# MINI_SAM_D51_015.net
KiCad netlist of a schematic drawn in EAGLE
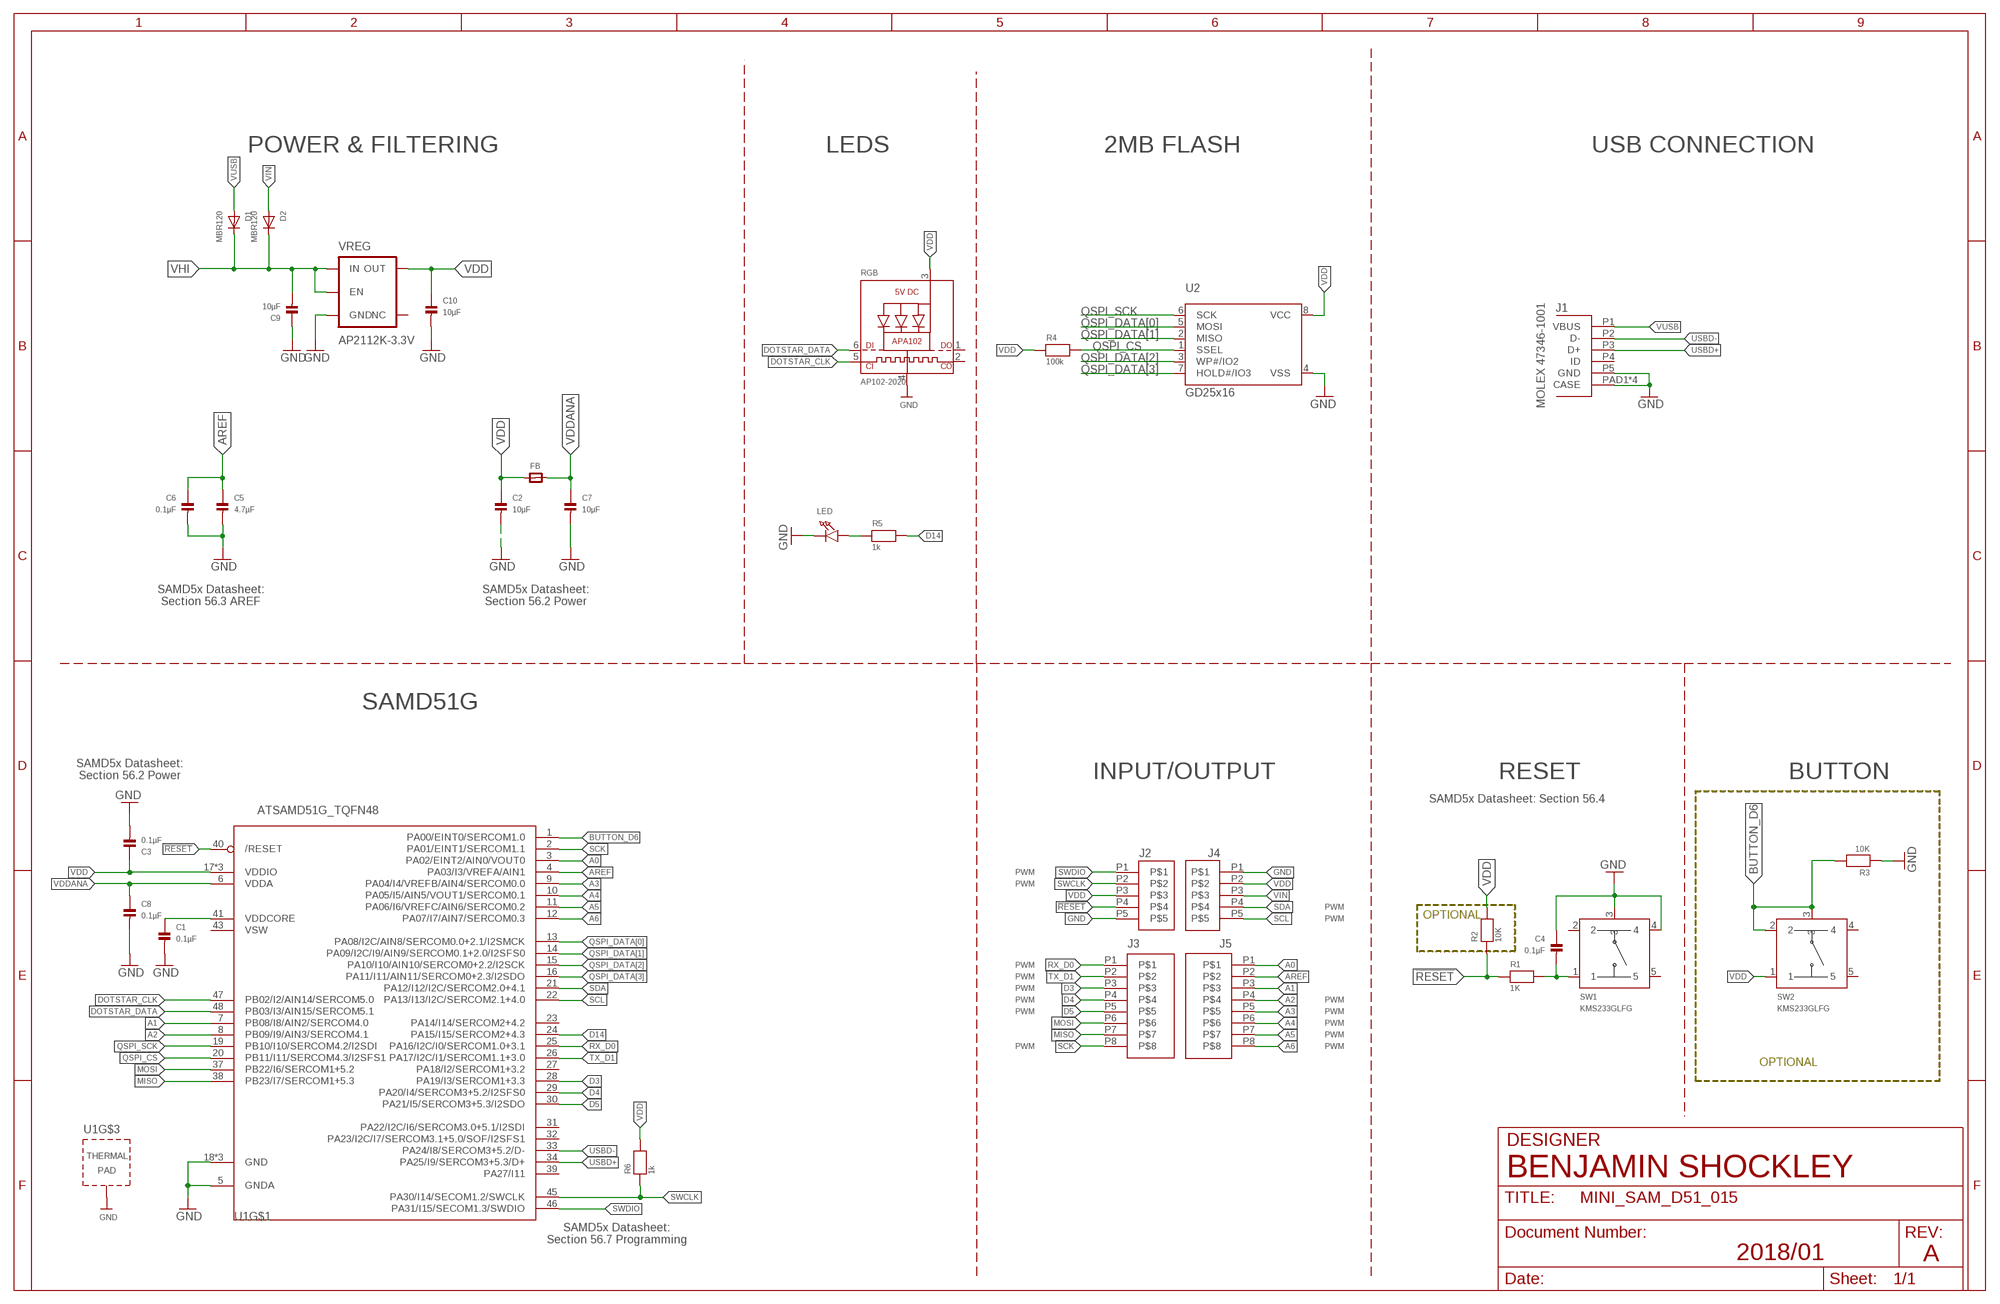
[diagram p0: schematic, sheet 1]

(export (version "E")
  (design (tool "Eeschema 10.0.6"))
  (components
    (comp (ref "C1")
      (value "0.1µF")
      (footprint "eagle-import:_0603MP")
      (libsource (lib "eagle-import") (part "CAP_CERAMIC_0603MP"))
    )
    (comp (ref "C2")
      (value "10µF")
      (footprint "eagle-import:_0603MP")
      (libsource (lib "eagle-import") (part "CAP_CERAMIC_0603MP"))
    )
    (comp (ref "C3")
      (value "0.1µF")
      (footprint "eagle-import:_0603MP")
      (libsource (lib "eagle-import") (part "CAP_CERAMIC_0603MP"))
    )
    (comp (ref "C4")
      (value "0.1µF")
      (footprint "eagle-import:_0603MP")
      (libsource (lib "eagle-import") (part "CAP_CERAMIC_0603MP"))
    )
    (comp (ref "C5")
      (value "4.7µF")
      (footprint "eagle-import:_0603MP")
      (libsource (lib "eagle-import") (part "CAP_CERAMIC_0603MP"))
    )
    (comp (ref "C6")
      (value "0.1µF")
      (footprint "eagle-import:_0603MP")
      (libsource (lib "eagle-import") (part "CAP_CERAMIC_0603MP"))
    )
    (comp (ref "C7")
      (value "10µF")
      (footprint "eagle-import:_0603MP")
      (libsource (lib "eagle-import") (part "CAP_CERAMIC_0603MP"))
    )
    (comp (ref "C8")
      (value "0.1µF")
      (footprint "eagle-import:_0603MP")
      (libsource (lib "eagle-import") (part "CAP_CERAMIC_0603MP"))
    )
    (comp (ref "C9")
      (value "10µF")
      (footprint "eagle-import:_0603MP")
      (libsource (lib "eagle-import") (part "CAP_CERAMIC_0603MP"))
    )
    (comp (ref "C10")
      (value "10µF")
      (footprint "eagle-import:_0603MP")
      (libsource (lib "eagle-import") (part "CAP_CERAMIC_0603MP"))
    )
    (comp (ref "D1")
      (value "MBR120")
      (footprint "eagle-import:SOD-123FL")
      (libsource (lib "eagle-import") (part "DIODE_SOD-123FL"))
    )
    (comp (ref "D2")
      (value "MBR120")
      (footprint "eagle-import:SOD-123FL")
      (libsource (lib "eagle-import") (part "DIODE_SOD-123FL"))
    )
    (comp (ref "FB")
      (value "FERRITE_0603MP")
      (footprint "eagle-import:_0603MP")
      (libsource (lib "eagle-import") (part "FERRITE_0603MP"))
    )
    (comp (ref "J1")
      (value "MOLEX_47346-100147346")
      (footprint "eagle-import:MOLEX_47346-1001")
      (libsource (lib "eagle-import") (part "MOLEX_47346-100147346"))
    )
    (comp (ref "J2")
      (value "1X5_HEADER_1.27MMCAST")
      (footprint "eagle-import:1X5_HEADER_1.27MM_CASTELLATED")
      (libsource (lib "eagle-import") (part "1X5_HEADER_1.27MMCAST"))
    )
    (comp (ref "J3")
      (value "1X8_HEADER_1.27MMCAST")
      (footprint "eagle-import:1X8_HEADER_1.27MM_CASTELLATED")
      (libsource (lib "eagle-import") (part "1X8_HEADER_1.27MMCAST"))
    )
    (comp (ref "J4")
      (value "1X5_HEADER_1.27MMCAST")
      (footprint "eagle-import:1X5_HEADER_1.27MM_CASTELLATED")
      (libsource (lib "eagle-import") (part "1X5_HEADER_1.27MMCAST"))
    )
    (comp (ref "J5")
      (value "1X8_HEADER_1.27MMCAST")
      (footprint "eagle-import:1X8_HEADER_1.27MM_CASTELLATED")
      (libsource (lib "eagle-import") (part "1X8_HEADER_1.27MMCAST"))
    )
    (comp (ref "LED")
      (value "LED0805_NOOUTLINE")
      (footprint "eagle-import:CHIPLED_0805_NOOUTLINE")
      (libsource (lib "eagle-import") (part "LED0805_NOOUTLINE"))
    )
    (comp (ref "R1")
      (value "1K")
      (footprint "eagle-import:_0603MP")
      (libsource (lib "eagle-import") (part "RESISTOR_0603MP"))
    )
    (comp (ref "R2")
      (value "10K")
      (footprint "eagle-import:_0603MP")
      (libsource (lib "eagle-import") (part "RESISTOR_0603MP"))
    )
    (comp (ref "R3")
      (value "10K")
      (footprint "eagle-import:_0603MP")
      (libsource (lib "eagle-import") (part "RESISTOR_0603MP"))
    )
    (comp (ref "R4")
      (value "100k")
      (footprint "eagle-import:_0603MP")
      (libsource (lib "eagle-import") (part "RESISTOR_0603MP"))
    )
    (comp (ref "R5")
      (value "1k")
      (footprint "eagle-import:_0603MP")
      (libsource (lib "eagle-import") (part "RESISTOR_0603MP"))
    )
    (comp (ref "R6")
      (value "1k")
      (footprint "eagle-import:_0603MP")
      (libsource (lib "eagle-import") (part "RESISTOR_0603MP"))
    )
    (comp (ref "RGB")
      (value "AP102-2020")
      (footprint "eagle-import:APA102_2020")
      (libsource (lib "eagle-import") (part "APA1022020"))
    )
    (comp (ref "SW1")
      (value "KMS233GLFG")
      (footprint "eagle-import:KMS_SWITCH")
      (libsource (lib "eagle-import") (part "KMS_SWITCHKMS"))
    )
    (comp (ref "SW2")
      (value "KMS233GLFG")
      (footprint "eagle-import:KMS_SWITCH")
      (libsource (lib "eagle-import") (part "KMS_SWITCHKMS"))
    )
    (comp (ref "U1")
      (value "ATSAMD51G_TQFN48")
      (footprint "eagle-import:TQFN48_7MM")
      (libsource (lib "eagle-import") (part "ATSAMD51G_TQFN48"))
    )
    (comp (ref "U2")
      (value "GD25x16")
      (footprint "eagle-import:USON8")
      (libsource (lib "eagle-import") (part "SPIFLASH_8PINUX"))
    )
    (comp (ref "VREG")
      (value "AP2112K-3.3V")
      (footprint "eagle-import:SOT23-5")
      (libsource (lib "eagle-import") (part "V_REG_AP2112K-3.3V"))
    )
  )
  (nets
    (net (code "1") (name "/VSW") (class "Default")
      (node (ref "U1") (pin "43") (pinfunction "VSW_43") (pintype "power_in"))
    )
    (net (code "2") (name "/~{RESET}") (class "Default")
      (node (ref "J2") (pin "P4") (pinfunction "P$4_P4") (pintype "bidirectional"))
      (node (ref "R1") (pin "1") (pinfunction "1_1") (pintype "passive"))
      (node (ref "R2") (pin "1") (pinfunction "1_1") (pintype "passive"))
      (node (ref "U1") (pin "40") (pinfunction "/RESET_40") (pintype "bidirectional"))
    )
    (net (code "3") (name "A0") (class "Default")
      (node (ref "J5") (pin "P1") (pinfunction "P$1_P1") (pintype "bidirectional"))
      (node (ref "U1") (pin "3") (pinfunction "PA02/EINT2/AIN0/VOUT0_3") (pintype "bidirectional"))
    )
    (net (code "4") (name "A1") (class "Default")
      (node (ref "J5") (pin "P3") (pinfunction "P$3_P3") (pintype "bidirectional"))
      (node (ref "U1") (pin "7") (pinfunction "PB08/I8/AIN2/SERCOM4.0_7") (pintype "bidirectional"))
    )
    (net (code "5") (name "A2") (class "Default")
      (node (ref "J5") (pin "P4") (pinfunction "P$4_P4") (pintype "bidirectional"))
      (node (ref "U1") (pin "8") (pinfunction "PB09/I9/AIN3/SERCOM4.1_8") (pintype "bidirectional"))
    )
    (net (code "6") (name "A3") (class "Default")
      (node (ref "J5") (pin "P5") (pinfunction "P$5_P5") (pintype "bidirectional"))
      (node (ref "U1") (pin "9") (pinfunction "PA04/I4/VREFB/AIN4/SERCOM0.0_9") (pintype "bidirectional"))
    )
    (net (code "7") (name "A4") (class "Default")
      (node (ref "J5") (pin "P6") (pinfunction "P$6_P6") (pintype "bidirectional"))
      (node (ref "U1") (pin "10") (pinfunction "PA05/I5/AIN5/VOUT1/SERCOM0.1_10") (pintype "bidirectional"))
    )
    (net (code "8") (name "A5") (class "Default")
      (node (ref "J5") (pin "P7") (pinfunction "P$7_P7") (pintype "bidirectional"))
      (node (ref "U1") (pin "11") (pinfunction "PA06/I6/VREFC/AIN6/SERCOM0.2_11") (pintype "bidirectional"))
    )
    (net (code "9") (name "A6") (class "Default")
      (node (ref "J5") (pin "P8") (pinfunction "P$8_P8") (pintype "bidirectional"))
      (node (ref "U1") (pin "12") (pinfunction "PA07/I7/AIN7/SERCOM0.3_12") (pintype "bidirectional"))
    )
    (net (code "10") (name "AREF") (class "Default")
      (node (ref "C5") (pin "1") (pinfunction "P$1_1") (pintype "passive"))
      (node (ref "C6") (pin "1") (pinfunction "P$1_1") (pintype "passive"))
      (node (ref "J5") (pin "P2") (pinfunction "P$2_P2") (pintype "bidirectional"))
      (node (ref "U1") (pin "4") (pinfunction "PA03/I3/VREFA/AIN1_4") (pintype "bidirectional"))
    )
    (net (code "11") (name "BUTTON_D6") (class "Default")
      (node (ref "R3") (pin "2") (pinfunction "2_2") (pintype "passive"))
      (node (ref "SW2") (pin "2") (pinfunction "2_2") (pintype "bidirectional"))
      (node (ref "SW2") (pin "3") (pinfunction "3_3") (pintype "bidirectional"))
      (node (ref "U1") (pin "1") (pinfunction "PA00/EINT0/SERCOM1.0_1") (pintype "bidirectional"))
    )
    (net (code "12") (name "D3") (class "Default")
      (node (ref "J3") (pin "P3") (pinfunction "P$3_P3") (pintype "bidirectional"))
      (node (ref "U1") (pin "28") (pinfunction "PA19/I3/SERCOM1+3.3_28") (pintype "bidirectional"))
    )
    (net (code "13") (name "D4") (class "Default")
      (node (ref "J3") (pin "P4") (pinfunction "P$4_P4") (pintype "bidirectional"))
      (node (ref "U1") (pin "29") (pinfunction "PA20/I4/SERCOM3+5.2/I2SFS0_29") (pintype "bidirectional"))
    )
    (net (code "14") (name "D5") (class "Default")
      (node (ref "J3") (pin "P5") (pinfunction "P$5_P5") (pintype "bidirectional"))
      (node (ref "U1") (pin "30") (pinfunction "PA21/I5/SERCOM3+5.3/I2SDO_30") (pintype "bidirectional"))
    )
    (net (code "15") (name "D14") (class "Default")
      (node (ref "R5") (pin "2") (pinfunction "2_2") (pintype "passive"))
      (node (ref "U1") (pin "24") (pinfunction "PA15/I15/SERCOM2+4.3_24") (pintype "bidirectional"))
    )
    (net (code "16") (name "DOTSTAR_CLK") (class "Default")
      (node (ref "RGB") (pin "5") (pinfunction "CKI_5") (pintype "input"))
      (node (ref "U1") (pin "47") (pinfunction "PB02/I2/AIN14/SERCOM5.0_47") (pintype "bidirectional"))
    )
    (net (code "17") (name "DOTSTAR_DATA") (class "Default")
      (node (ref "RGB") (pin "6") (pinfunction "DI_6") (pintype "input"))
      (node (ref "U1") (pin "48") (pinfunction "PB03/I3/AIN15/SERCOM5.1_48") (pintype "bidirectional"))
    )
    (net (code "18") (name "GND") (class "Default")
      (node (ref "C1") (pin "2") (pinfunction "P$2_2") (pintype "passive"))
      (node (ref "C10") (pin "2") (pinfunction "P$2_2") (pintype "passive"))
      (node (ref "C2") (pin "2") (pinfunction "P$2_2") (pintype "passive"))
      (node (ref "C3") (pin "2") (pinfunction "P$2_2") (pintype "passive"))
      (node (ref "C4") (pin "1") (pinfunction "P$1_1") (pintype "passive"))
      (node (ref "C5") (pin "2") (pinfunction "P$2_2") (pintype "passive"))
      (node (ref "C6") (pin "2") (pinfunction "P$2_2") (pintype "passive"))
      (node (ref "C7") (pin "2") (pinfunction "P$2_2") (pintype "passive"))
      (node (ref "C8") (pin "2") (pinfunction "P$2_2") (pintype "passive"))
      (node (ref "C9") (pin "1") (pinfunction "P$1_1") (pintype "passive"))
      (node (ref "J1") (pin "P5") (pinfunction "GND_P5") (pintype "power_in"))
      (node (ref "J1") (pin "PAD1") (pinfunction "CASE_PAD1") (pintype "bidirectional"))
      (node (ref "J1") (pin "PAD2") (pinfunction "CASE_PAD2") (pintype "bidirectional"))
      (node (ref "J1") (pin "PAD3") (pinfunction "CASE_PAD3") (pintype "bidirectional"))
      (node (ref "J1") (pin "PAD4") (pinfunction "CASE_PAD4") (pintype "bidirectional"))
      (node (ref "J2") (pin "P5") (pinfunction "P$5_P5") (pintype "bidirectional"))
      (node (ref "J4") (pin "P1") (pinfunction "P$1_P1") (pintype "bidirectional"))
      (node (ref "LED") (pin "C") (pinfunction "C_C") (pintype "passive"))
      (node (ref "R3") (pin "1") (pinfunction "1_1") (pintype "passive"))
      (node (ref "RGB") (pin "4") (pinfunction "GND_4") (pintype "power_in"))
      (node (ref "SW1") (pin "3") (pinfunction "3_3") (pintype "bidirectional"))
      (node (ref "SW1") (pin "4") (pinfunction "4_4") (pintype "bidirectional"))
      (node (ref "U1") (pin "18") (pinfunction "GND_18") (pintype "power_in"))
      (node (ref "U1") (pin "35") (pinfunction "GND_35") (pintype "power_in"))
      (node (ref "U1") (pin "42") (pinfunction "GND_42") (pintype "power_in"))
      (node (ref "U1") (pin "5") (pinfunction "GNDA_5") (pintype "power_in"))
      (node (ref "U1") (pin "THERMAL") (pinfunction "TP_THERMAL") (pintype "power_in"))
      (node (ref "U2") (pin "4") (pinfunction "VSS_4") (pintype "bidirectional"))
      (node (ref "VREG") (pin "2") (pinfunction "GND_2") (pintype "input"))
    )
    (net (code "19") (name "MISO") (class "Default")
      (node (ref "J3") (pin "P7") (pinfunction "P$7_P7") (pintype "bidirectional"))
      (node (ref "U1") (pin "38") (pinfunction "PB23/I7/SERCOM1+5.3_38") (pintype "bidirectional"))
    )
    (net (code "20") (name "MOSI") (class "Default")
      (node (ref "J3") (pin "P6") (pinfunction "P$6_P6") (pintype "bidirectional"))
      (node (ref "U1") (pin "37") (pinfunction "PB22/I6/SERCOM1+5.2_37") (pintype "bidirectional"))
    )
    (net (code "21") (name "Net-(C1-P$1)") (class "Default")
      (node (ref "C1") (pin "1") (pinfunction "P$1_1") (pintype "passive"))
      (node (ref "U1") (pin "41") (pinfunction "VDDCORE_41") (pintype "power_in"))
    )
    (net (code "22") (name "Net-(C4-P$2)") (class "Default")
      (node (ref "C4") (pin "2") (pinfunction "P$2_2") (pintype "passive"))
      (node (ref "R1") (pin "2") (pinfunction "2_2") (pintype "passive"))
      (node (ref "SW1") (pin "1") (pinfunction "1_1") (pintype "bidirectional"))
    )
    (net (code "23") (name "Net-(LED-PadA)") (class "Default")
      (node (ref "LED") (pin "A") (pinfunction "A_A") (pintype "passive"))
      (node (ref "R5") (pin "1") (pinfunction "1_1") (pintype "passive"))
    )
    (net (code "24") (name "QSPI_CS") (class "Default")
      (node (ref "R4") (pin "2") (pinfunction "2_2") (pintype "passive"))
      (node (ref "U1") (pin "20") (pinfunction "PB11/I11/SERCOM4.3/I2SFS1_20") (pintype "bidirectional"))
      (node (ref "U2") (pin "1") (pinfunction "SSEL_1") (pintype "bidirectional"))
    )
    (net (code "25") (name "QSPI_DATA[0]") (class "Default")
      (node (ref "U1") (pin "13") (pinfunction "PA08/I2C/AIN8/SERCOM0.0+2.1/I2SMCK_13") (pintype "bidirectional"))
      (node (ref "U2") (pin "5") (pinfunction "MOSI_5") (pintype "bidirectional"))
    )
    (net (code "26") (name "QSPI_DATA[1]") (class "Default")
      (node (ref "U1") (pin "14") (pinfunction "PA09/I2C/I9/AIN9/SERCOM0.1+2.0/I2SFS0_14") (pintype "bidirectional"))
      (node (ref "U2") (pin "2") (pinfunction "MISO_2") (pintype "bidirectional"))
    )
    (net (code "27") (name "QSPI_DATA[2]") (class "Default")
      (node (ref "U1") (pin "15") (pinfunction "PA10/I10/AIN10/SERCOM0+2.2/I2SCK_15") (pintype "bidirectional"))
      (node (ref "U2") (pin "3") (pinfunction "WP#/IO2_3") (pintype "bidirectional"))
    )
    (net (code "28") (name "QSPI_DATA[3]") (class "Default")
      (node (ref "U1") (pin "16") (pinfunction "PA11/I11/AIN11/SERCOM0+2.3/I2SDO_16") (pintype "bidirectional"))
      (node (ref "U2") (pin "7") (pinfunction "HOLD#/IO3_7") (pintype "bidirectional"))
    )
    (net (code "29") (name "QSPI_SCK") (class "Default")
      (node (ref "U1") (pin "19") (pinfunction "PB10/I10/SERCOM4.2/I2SDI_19") (pintype "bidirectional"))
      (node (ref "U2") (pin "6") (pinfunction "SCK_6") (pintype "bidirectional"))
    )
    (net (code "30") (name "RX_D0") (class "Default")
      (node (ref "J3") (pin "P1") (pinfunction "P$1_P1") (pintype "bidirectional"))
      (node (ref "U1") (pin "25") (pinfunction "PA16/I2C/I0/SERCOM1.0+3.1_25") (pintype "bidirectional"))
    )
    (net (code "31") (name "SCK") (class "Default")
      (node (ref "J3") (pin "P8") (pinfunction "P$8_P8") (pintype "bidirectional"))
      (node (ref "U1") (pin "2") (pinfunction "PA01/EINT1/SERCOM1.1_2") (pintype "bidirectional"))
    )
    (net (code "32") (name "SCL") (class "Default")
      (node (ref "J4") (pin "P5") (pinfunction "P$5_P5") (pintype "bidirectional"))
      (node (ref "U1") (pin "22") (pinfunction "PA13/I13/I2C/SERCOM2.1+4.0_22") (pintype "bidirectional"))
    )
    (net (code "33") (name "SDA") (class "Default")
      (node (ref "J4") (pin "P4") (pinfunction "P$4_P4") (pintype "bidirectional"))
      (node (ref "U1") (pin "21") (pinfunction "PA12/I12/I2C/SERCOM2.0+4.1_21") (pintype "bidirectional"))
    )
    (net (code "34") (name "SWCLK") (class "Default")
      (node (ref "J2") (pin "P2") (pinfunction "P$2_P2") (pintype "bidirectional"))
      (node (ref "R6") (pin "1") (pinfunction "1_1") (pintype "passive"))
      (node (ref "U1") (pin "45") (pinfunction "PA30/I14/SECOM1.2/SWCLK_45") (pintype "bidirectional"))
    )
    (net (code "35") (name "SWDIO") (class "Default")
      (node (ref "J2") (pin "P1") (pinfunction "P$1_P1") (pintype "bidirectional"))
      (node (ref "U1") (pin "46") (pinfunction "PA31/I15/SECOM1.3/SWDIO_46") (pintype "bidirectional"))
    )
    (net (code "36") (name "TX_D1") (class "Default")
      (node (ref "J3") (pin "P2") (pinfunction "P$2_P2") (pintype "bidirectional"))
      (node (ref "U1") (pin "26") (pinfunction "PA17/I2C/I1/SERCOM1.1+3.0_26") (pintype "bidirectional"))
    )
    (net (code "37") (name "USBD+") (class "Default")
      (node (ref "J1") (pin "P3") (pinfunction "D+_P3") (pintype "bidirectional"))
      (node (ref "U1") (pin "34") (pinfunction "PA25/I9/SERCOM3+5.3/D+_34") (pintype "bidirectional"))
    )
    (net (code "38") (name "USBD-") (class "Default")
      (node (ref "J1") (pin "P2") (pinfunction "D-_P2") (pintype "bidirectional"))
      (node (ref "U1") (pin "33") (pinfunction "PA24/I8/SERCOM3+5.2/D-_33") (pintype "bidirectional"))
    )
    (net (code "39") (name "VDD") (class "Default")
      (node (ref "C10") (pin "1") (pinfunction "P$1_1") (pintype "passive"))
      (node (ref "C2") (pin "1") (pinfunction "P$1_1") (pintype "passive"))
      (node (ref "C3") (pin "1") (pinfunction "P$1_1") (pintype "passive"))
      (node (ref "FB") (pin "1") (pinfunction "P$1_1") (pintype "passive"))
      (node (ref "J2") (pin "P3") (pinfunction "P$3_P3") (pintype "bidirectional"))
      (node (ref "J4") (pin "P2") (pinfunction "P$2_P2") (pintype "bidirectional"))
      (node (ref "R2") (pin "2") (pinfunction "2_2") (pintype "passive"))
      (node (ref "R4") (pin "1") (pinfunction "1_1") (pintype "passive"))
      (node (ref "R6") (pin "2") (pinfunction "2_2") (pintype "passive"))
      (node (ref "RGB") (pin "3") (pinfunction "VDD_3") (pintype "power_in"))
      (node (ref "SW2") (pin "1") (pinfunction "1_1") (pintype "bidirectional"))
      (node (ref "U1") (pin "17") (pinfunction "VDDIO_17") (pintype "power_in"))
      (node (ref "U1") (pin "36") (pinfunction "VDDIO_36") (pintype "power_in"))
      (node (ref "U1") (pin "44") (pinfunction "VDDIO_44") (pintype "power_in"))
      (node (ref "U2") (pin "8") (pinfunction "VCC_8") (pintype "bidirectional"))
      (node (ref "VREG") (pin "5") (pinfunction "OUT_5") (pintype "passive"))
    )
    (net (code "40") (name "VDDANA") (class "Default")
      (node (ref "C7") (pin "1") (pinfunction "P$1_1") (pintype "passive"))
      (node (ref "C8") (pin "1") (pinfunction "P$1_1") (pintype "passive"))
      (node (ref "FB") (pin "2") (pinfunction "P$2_2") (pintype "passive"))
      (node (ref "U1") (pin "6") (pinfunction "VDDA_6") (pintype "power_in"))
    )
    (net (code "41") (name "VHI") (class "Default")
      (node (ref "C9") (pin "2") (pinfunction "P$2_2") (pintype "passive"))
      (node (ref "D1") (pin "C") (pinfunction "C_C") (pintype "passive"))
      (node (ref "D2") (pin "C") (pinfunction "C_C") (pintype "passive"))
      (node (ref "VREG") (pin "1") (pinfunction "IN_1") (pintype "input"))
      (node (ref "VREG") (pin "3") (pinfunction "EN_3") (pintype "input"))
    )
    (net (code "42") (name "VIN") (class "Default")
      (node (ref "D2") (pin "A") (pinfunction "A_A") (pintype "passive"))
      (node (ref "J4") (pin "P3") (pinfunction "P$3_P3") (pintype "bidirectional"))
    )
    (net (code "43") (name "VUSB") (class "Default")
      (node (ref "D1") (pin "A") (pinfunction "A_A") (pintype "passive"))
      (node (ref "J1") (pin "P1") (pinfunction "VBUS_P1") (pintype "power_in"))
    )
    (net (code "44") (name "unconnected-(J1-ID-PadP4)") (class "Default")
      (node (ref "J1") (pin "P4") (pinfunction "ID_P4") (pintype "bidirectional"))
    )
    (net (code "45") (name "unconnected-(RGB-CKO-Pad2)") (class "Default")
      (node (ref "RGB") (pin "2") (pinfunction "CKO_2") (pintype "output"))
    )
    (net (code "46") (name "unconnected-(RGB-DO-Pad1)") (class "Default")
      (node (ref "RGB") (pin "1") (pinfunction "DO_1") (pintype "output"))
    )
    (net (code "47") (name "unconnected-(SW1-Pad2)") (class "Default")
      (node (ref "SW1") (pin "2") (pinfunction "2_2") (pintype "bidirectional"))
    )
    (net (code "48") (name "unconnected-(SW1-Pad5)") (class "Default")
      (node (ref "SW1") (pin "5") (pinfunction "5_5") (pintype "bidirectional"))
    )
    (net (code "49") (name "unconnected-(SW2-Pad4)") (class "Default")
      (node (ref "SW2") (pin "4") (pinfunction "4_4") (pintype "bidirectional"))
    )
    (net (code "50") (name "unconnected-(SW2-Pad5)") (class "Default")
      (node (ref "SW2") (pin "5") (pinfunction "5_5") (pintype "bidirectional"))
    )
    (net (code "51") (name "unconnected-(U1A-PA14{slash}I14{slash}SERCOM2+4.2-Pad23)") (class "Default")
      (node (ref "U1") (pin "23") (pinfunction "PA14/I14/SERCOM2+4.2_23") (pintype "bidirectional"))
    )
    (net (code "52") (name "unconnected-(U1A-PA18{slash}I2{slash}SERCOM1+3.2-Pad27)") (class "Default")
      (node (ref "U1") (pin "27") (pinfunction "PA18/I2/SERCOM1+3.2_27") (pintype "bidirectional"))
    )
    (net (code "53") (name "unconnected-(U1A-PA22{slash}I2C{slash}I6{slash}SERCOM3.0+5.1{slash}I2SDI-Pad31)") (class "Default")
      (node (ref "U1") (pin "31") (pinfunction "PA22/I2C/I6/SERCOM3.0+5.1/I2SDI_31") (pintype "bidirectional"))
    )
    (net (code "54") (name "unconnected-(U1A-PA23{slash}I2C{slash}I7{slash}SERCOM3.1+5.0{slash}SOF{slash}I2SFS1-Pad32)") (class "Default")
      (node (ref "U1") (pin "32") (pinfunction "PA23/I2C/I7/SERCOM3.1+5.0/SOF/I2SFS1_32") (pintype "bidirectional"))
    )
    (net (code "55") (name "unconnected-(U1A-PA27{slash}I11-Pad39)") (class "Default")
      (node (ref "U1") (pin "39") (pinfunction "PA27/I11_39") (pintype "bidirectional"))
    )
    (net (code "56") (name "unconnected-(VREG-NC-Pad4)") (class "Default")
      (node (ref "VREG") (pin "4") (pinfunction "NC_4") (pintype "input"))
    )
  )
)
